# 24_063_24_069.net
KiCad netlist of a schematic drawn in Altium Designer
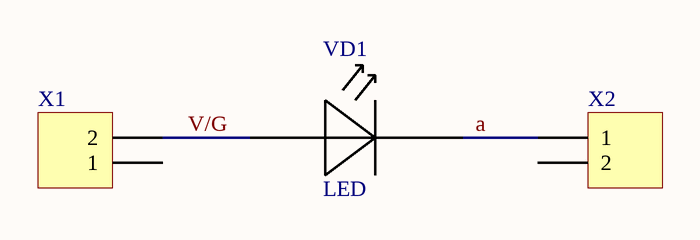
[diagram p0: 24.063_24.069.SchDoc]

(export (version "E")
  (design (tool "Eeschema 10.0.6"))
  (components
    (comp (ref "VD1") (value "LED") (footprint "LED 24.063") (libsource (lib "msp_SchLib") (part "LED")))
    (comp (ref "X1")
      (value "Header 2")
      (footprint "HDR1X2")
      (description "Header, 2-Pin")
      (fields (field (name "PUBLISHER") "Altium Limited"))
      (libsource (lib "") (part "Header 2_1"))
    )
    (comp (ref "X2")
      (value "Header 2")
      (footprint "HDR1X2")
      (description "Header, 2-Pin")
      (fields (field (name "PUBLISHER") "Altium Limited"))
      (libsource (lib "Miscellaneous Connectors") (part "Header 2"))
    )
  )
  (nets
    (net (code "1") (name "/V{slash}G") (class "Default")
      (node (ref "VD1") (pin "1") (pinfunction "1_1") (pintype "passive"))
      (node (ref "X1") (pin "2") (pinfunction "2_2") (pintype "passive"))
    )
    (net (code "2") (name "/a") (class "Default")
      (node (ref "VD1") (pin "2") (pinfunction "2_2") (pintype "passive"))
      (node (ref "X2") (pin "1") (pinfunction "1_1") (pintype "passive"))
    )
    (net (code "3") (name "unconnected-(X1-Pad1)") (class "Default")
      (node (ref "X1") (pin "1") (pinfunction "1_1") (pintype "passive"))
    )
    (net (code "4") (name "unconnected-(X2-Pad2)") (class "Default")
      (node (ref "X2") (pin "2") (pinfunction "2_2") (pintype "passive"))
    )
  )
)
